# Papra_v0_3.net
KiCad netlist of a schematic drawn in EAGLE
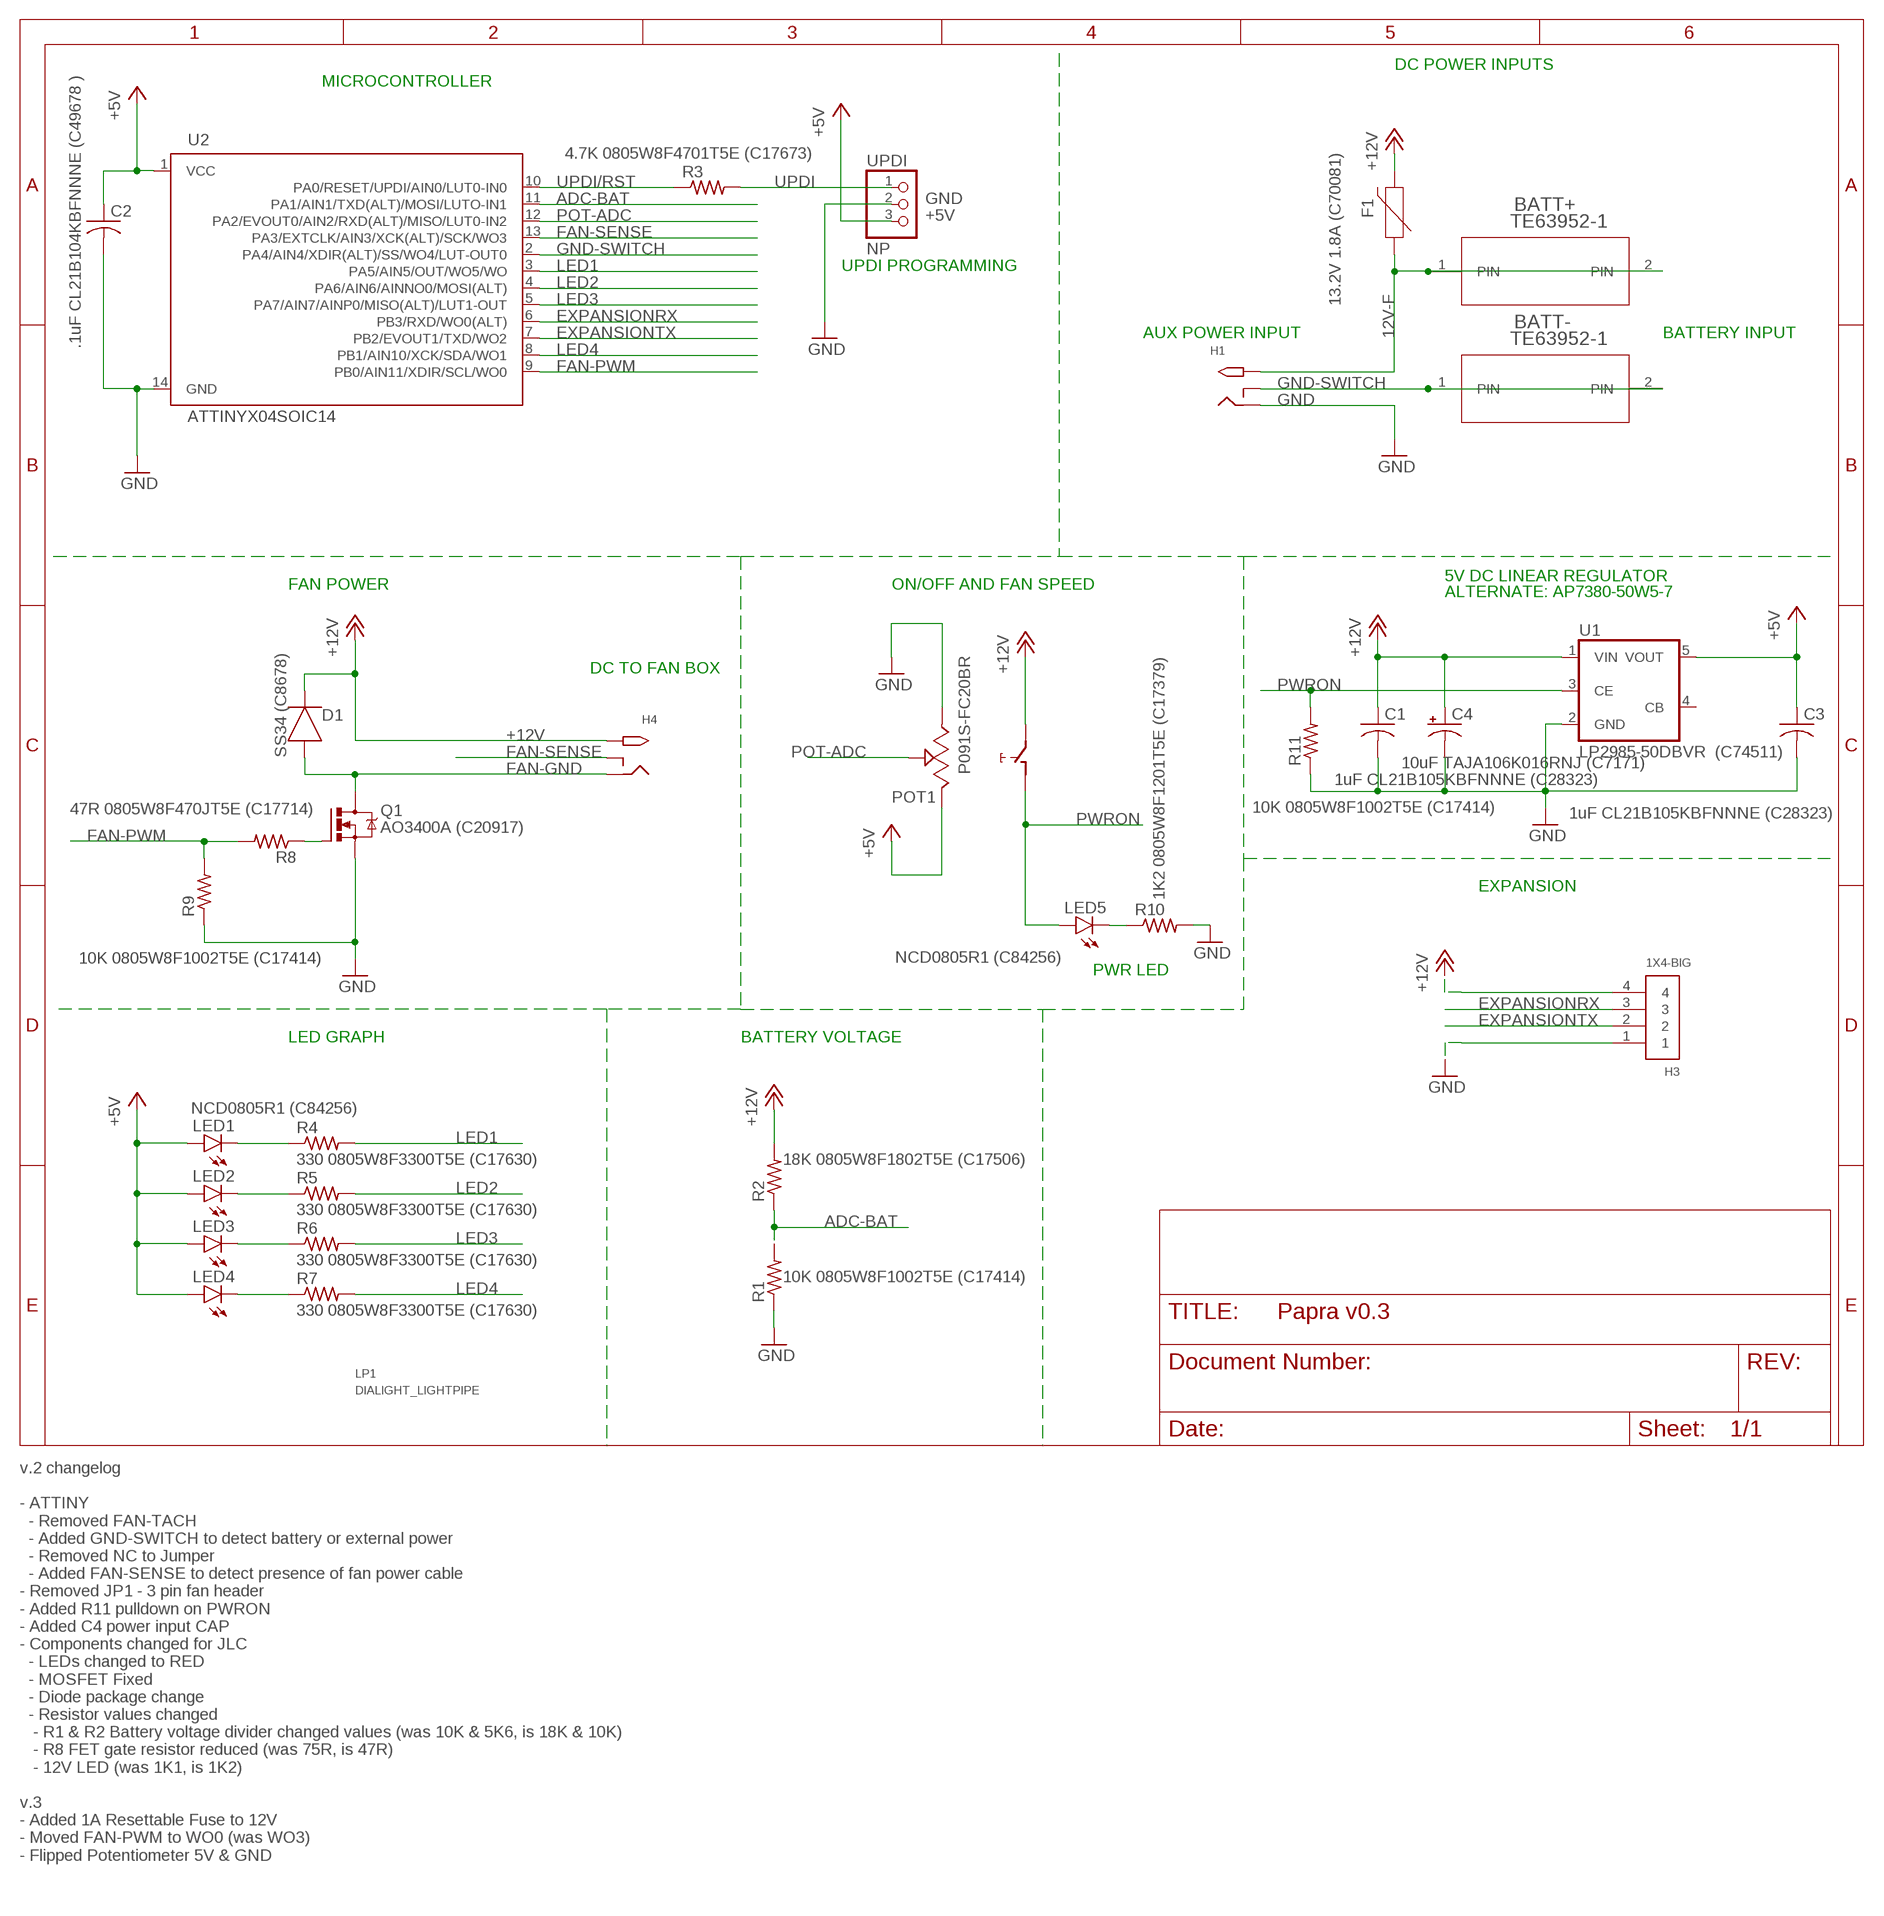
[diagram p0: schematic, sheet 1]

(export (version "E")
  (design (tool "Eeschema 10.0.6"))
  (components
    (comp (ref "BATT+")
      (value "TE63952-1")
      (footprint "eagle-import:TE63952-1")
      (libsource (lib "eagle-import") (part "TE63952-1"))
    )
    (comp (ref "BATT-")
      (value "TE63952-1")
      (footprint "eagle-import:TE63952-1")
      (libsource (lib "eagle-import") (part "TE63952-1"))
    )
    (comp (ref "C1")
      (value "1uF CL21B105KBFNNNE (C28323)")
      (footprint "eagle-import:C0805")
      (libsource (lib "eagle-import") (part "C-USC0805"))
    )
    (comp (ref "C2")
      (value ".1uF CL21B104KBFNNNE (C49678 )")
      (footprint "eagle-import:C0805")
      (libsource (lib "eagle-import") (part "C-USC0805"))
    )
    (comp (ref "C3")
      (value "1uF CL21B105KBFNNNE (C28323)")
      (footprint "eagle-import:C0805")
      (libsource (lib "eagle-import") (part "C-USC0805"))
    )
    (comp (ref "C4")
      (value "10uF TAJA106K016RNJ (C7171)")
      (footprint "eagle-import:A_3216-18R")
      (libsource (lib "eagle-import") (part "CPOL-USA/3216-18R"))
    )
    (comp (ref "D1")
      (value "SS34 (C8678)")
      (footprint "eagle-import:DIOM5226X290N")
      (libsource (lib "eagle-import") (part "DIODEDO-214AC(SMA)"))
    )
    (comp (ref "F1")
      (value "13.2V 1.8A (C70081)")
      (footprint "eagle-import:1206")
      (libsource (lib "eagle-import") (part "PPTC_HALF-AMP"))
    )
    (comp (ref "H1")
      (value "M-CUI-PJ-066A")
      (footprint "eagle-import:DCJACK-PJ-066A")
      (libsource (lib "eagle-import") (part "PJ-066A"))
    )
    (comp (ref "H3")
      (value "1X4-BIG")
      (footprint "eagle-import:1X04-BIG")
      (libsource (lib "eagle-import") (part "1X4-BIG"))
    )
    (comp (ref "H4")
      (value "M-CUI-PJ-066A")
      (footprint "eagle-import:DCJACK-PJ-066A")
      (libsource (lib "eagle-import") (part "PJ-066A"))
    )
    (comp (ref "LED1")
      (value "NCD0805R1 (C84256)")
      (footprint "eagle-import:CHIPLED_0805")
      (libsource (lib "eagle-import") (part "LEDCHIPLED_0805"))
    )
    (comp (ref "LED2")
      (value "NCD0805R1 (C84256)")
      (footprint "eagle-import:CHIPLED_0805")
      (libsource (lib "eagle-import") (part "LEDCHIPLED_0805"))
    )
    (comp (ref "LED3")
      (value "NCD0805R1 (C84256)")
      (footprint "eagle-import:CHIPLED_0805")
      (libsource (lib "eagle-import") (part "LEDCHIPLED_0805"))
    )
    (comp (ref "LED4")
      (value "NCD0805R1 (C84256)")
      (footprint "eagle-import:CHIPLED_0805")
      (libsource (lib "eagle-import") (part "LEDCHIPLED_0805"))
    )
    (comp (ref "LED5")
      (value "NCD0805R1 (C84256)")
      (footprint "eagle-import:CHIPLED_0805")
      (libsource (lib "eagle-import") (part "LEDCHIPLED_0805"))
    )
    (comp (ref "LP1")
      (value "DIALIGHT_LIGHTPIPE")
      (footprint "eagle-import:DIALIGHT_5151020F__LEDS")
      (libsource (lib "eagle-import") (part "DIALIGHT_LIGHTPIPE"))
    )
    (comp (ref "POT1")
      (value "P091S-FC20BR")
      (footprint "eagle-import:P091S-FC20BR")
      (libsource (lib "eagle-import") (part "P091S-FC20BR"))
    )
    (comp (ref "Q1")
      (value "AO3400A (C20917)")
      (footprint "eagle-import:SOT23")
      (fields (field (name "MANUFACTURER") "ON Semiconductor") (field (name "MPN") "BSS123L"))
      (libsource (lib "eagle-import") (part "NMOSFET_-SOT23BSS123"))
    )
    (comp (ref "R1")
      (value "10K 0805W8F1002T5E (C17414)")
      (footprint "eagle-import:R0805")
      (libsource (lib "eagle-import") (part "R-US_R0805"))
    )
    (comp (ref "R2")
      (value "18K 0805W8F1802T5E (C17506)")
      (footprint "eagle-import:R0805")
      (libsource (lib "eagle-import") (part "R-US_R0805"))
    )
    (comp (ref "R3")
      (value "4.7K 0805W8F4701T5E (C17673)")
      (footprint "eagle-import:R0805")
      (libsource (lib "eagle-import") (part "R-US_R0805"))
    )
    (comp (ref "R4")
      (value "330 0805W8F3300T5E (C17630)")
      (footprint "eagle-import:R0805")
      (libsource (lib "eagle-import") (part "R-US_R0805"))
    )
    (comp (ref "R5")
      (value "330 0805W8F3300T5E (C17630)")
      (footprint "eagle-import:R0805")
      (libsource (lib "eagle-import") (part "R-US_R0805"))
    )
    (comp (ref "R6")
      (value "330 0805W8F3300T5E (C17630)")
      (footprint "eagle-import:R0805")
      (libsource (lib "eagle-import") (part "R-US_R0805"))
    )
    (comp (ref "R7")
      (value "330 0805W8F3300T5E (C17630)")
      (footprint "eagle-import:R0805")
      (libsource (lib "eagle-import") (part "R-US_R0805"))
    )
    (comp (ref "R8")
      (value "47R 0805W8F470JT5E (C17714)")
      (footprint "eagle-import:R0805")
      (libsource (lib "eagle-import") (part "R-US_R0805"))
    )
    (comp (ref "R9")
      (value "10K 0805W8F1002T5E (C17414)")
      (footprint "eagle-import:R0805")
      (libsource (lib "eagle-import") (part "R-US_R0805"))
    )
    (comp (ref "R10")
      (value "1K2 0805W8F1201T5E (C17379)")
      (footprint "eagle-import:R0805")
      (libsource (lib "eagle-import") (part "R-US_R0805"))
    )
    (comp (ref "R11")
      (value "10K 0805W8F1002T5E (C17414)")
      (footprint "eagle-import:R0805")
      (libsource (lib "eagle-import") (part "R-US_R0805"))
    )
    (comp (ref "U1")
      (value "LP2985-50DBVR (C74511)")
      (footprint "eagle-import:SOT25")
      (libsource (lib "eagle-import") (part "TS520533"))
    )
    (comp (ref "U2")
      (value "ATTINYX04SOIC14")
      (footprint "eagle-import:SOIC127P600X144-14")
      (libsource (lib "eagle-import") (part "ATTINYX04SOIC14"))
    )
    (comp (ref "UPDI")
      (value "NP")
      (footprint "eagle-import:1X03")
      (libsource (lib "eagle-import") (part "PINHD-1X3"))
    )
  )
  (nets
    (net (code "1") (name "+5V") (class "Default")
      (node (ref "C2") (pin "1") (pinfunction "1_1") (pintype "passive"))
      (node (ref "C3") (pin "1") (pinfunction "1_1") (pintype "passive"))
      (node (ref "LED1") (pin "A") (pinfunction "A_A") (pintype "passive"))
      (node (ref "LED2") (pin "A") (pinfunction "A_A") (pintype "passive"))
      (node (ref "LED3") (pin "A") (pinfunction "A_A") (pintype "passive"))
      (node (ref "LED4") (pin "A") (pinfunction "A_A") (pintype "passive"))
      (node (ref "POT1") (pin "3") (pinfunction "3_3") (pintype "passive"))
      (node (ref "U1") (pin "5") (pinfunction "VOUT_5") (pintype "passive"))
      (node (ref "U2") (pin "1") (pinfunction "VCC_1") (pintype "power_in"))
      (node (ref "UPDI") (pin "3") (pinfunction "3_3") (pintype "passive"))
    )
    (net (code "2") (name "+12V") (class "Default")
      (node (ref "C1") (pin "1") (pinfunction "1_1") (pintype "passive"))
      (node (ref "C4") (pin "+") (pinfunction "+_+") (pintype "passive"))
      (node (ref "D1") (pin "1") (pinfunction "C_1") (pintype "passive"))
      (node (ref "F1") (pin "2") (pinfunction "2_2") (pintype "bidirectional"))
      (node (ref "H3") (pin "4") (pinfunction "4_4") (pintype "bidirectional"))
      (node (ref "H4") (pin "PWR") (pinfunction "TIP_PWR") (pintype "bidirectional"))
      (node (ref "POT1") (pin "NO") (pinfunction "5_NO") (pintype "passive"))
      (node (ref "R2") (pin "2") (pinfunction "2_2") (pintype "passive"))
      (node (ref "U1") (pin "1") (pinfunction "VIN_1") (pintype "input"))
    )
    (net (code "3") (name "/12V-F") (class "Default")
      (node (ref "BATT+") (pin "1") (pinfunction "PIN_1") (pintype "passive"))
      (node (ref "BATT+") (pin "2") (pinfunction "PIN_2") (pintype "passive"))
      (node (ref "F1") (pin "1") (pinfunction "1_1") (pintype "bidirectional"))
      (node (ref "H1") (pin "PWR") (pinfunction "TIP_PWR") (pintype "bidirectional"))
    )
    (net (code "4") (name "/ADC-BAT") (class "Default")
      (node (ref "R1") (pin "2") (pinfunction "2_2") (pintype "passive"))
      (node (ref "R2") (pin "1") (pinfunction "1_1") (pintype "passive"))
      (node (ref "U2") (pin "11") (pinfunction "PA1/AIN1/TXD(ALT)/MOSI/LUTO-IN1_11") (pintype "bidirectional"))
    )
    (net (code "5") (name "/EXPANSIONRX") (class "Default")
      (node (ref "H3") (pin "3") (pinfunction "3_3") (pintype "bidirectional"))
      (node (ref "U2") (pin "6") (pinfunction "PB3/RXD/WO0(ALT)_6") (pintype "bidirectional"))
    )
    (net (code "6") (name "/EXPANSIONTX") (class "Default")
      (node (ref "H3") (pin "2") (pinfunction "2_2") (pintype "bidirectional"))
      (node (ref "U2") (pin "7") (pinfunction "PB2/EVOUT1/TXD/WO2_7") (pintype "bidirectional"))
    )
    (net (code "7") (name "/FAN-GND") (class "Default")
      (node (ref "D1") (pin "2") (pinfunction "A_2") (pintype "passive"))
      (node (ref "H4") (pin "GND") (pinfunction "RING_GND") (pintype "bidirectional"))
      (node (ref "Q1") (pin "3") (pinfunction "D_3") (pintype "passive"))
    )
    (net (code "8") (name "/FAN-PWM") (class "Default")
      (node (ref "R8") (pin "2") (pinfunction "2_2") (pintype "passive"))
      (node (ref "R9") (pin "2") (pinfunction "2_2") (pintype "passive"))
      (node (ref "U2") (pin "9") (pinfunction "PB0/AIN11/XDIR/SCL/WO0_9") (pintype "bidirectional"))
    )
    (net (code "9") (name "/FAN-SENSE") (class "Default")
      (node (ref "H4") (pin "GNDBREAK") (pinfunction "RING_SW_GNDBREAK") (pintype "bidirectional"))
      (node (ref "U2") (pin "13") (pinfunction "PA3/EXTCLK/AIN3/XCK(ALT)/SCK/WO3_13") (pintype "bidirectional"))
    )
    (net (code "10") (name "/GND-SWITCH") (class "Default")
      (node (ref "BATT-") (pin "1") (pinfunction "PIN_1") (pintype "passive"))
      (node (ref "BATT-") (pin "2") (pinfunction "PIN_2") (pintype "passive"))
      (node (ref "H1") (pin "GNDBREAK") (pinfunction "RING_SW_GNDBREAK") (pintype "bidirectional"))
      (node (ref "U2") (pin "2") (pinfunction "PA4/AIN4/XDIR(ALT)/SS/WO4/LUT-OUT0_2") (pintype "bidirectional"))
    )
    (net (code "11") (name "/LED1") (class "Default")
      (node (ref "R4") (pin "2") (pinfunction "2_2") (pintype "passive"))
      (node (ref "U2") (pin "3") (pinfunction "PA5/AIN5/OUT/WO5/WO_3") (pintype "bidirectional"))
    )
    (net (code "12") (name "/LED2") (class "Default")
      (node (ref "R5") (pin "2") (pinfunction "2_2") (pintype "passive"))
      (node (ref "U2") (pin "4") (pinfunction "PA6/AIN6/AINNO0/MOSI(ALT)_4") (pintype "bidirectional"))
    )
    (net (code "13") (name "/LED3") (class "Default")
      (node (ref "R6") (pin "2") (pinfunction "2_2") (pintype "passive"))
      (node (ref "U2") (pin "5") (pinfunction "PA7/AIN7/AINP0/MISO(ALT)/LUT1-OUT_5") (pintype "bidirectional"))
    )
    (net (code "14") (name "/LED4") (class "Default")
      (node (ref "R7") (pin "2") (pinfunction "2_2") (pintype "passive"))
      (node (ref "U2") (pin "8") (pinfunction "PB1/AIN10/XCK/SDA/WO1_8") (pintype "bidirectional"))
    )
    (net (code "15") (name "/POT-ADC") (class "Default")
      (node (ref "POT1") (pin "2") (pinfunction "2_2") (pintype "passive"))
      (node (ref "U2") (pin "12") (pinfunction "PA2/EVOUT0/AIN2/RXD(ALT)/MISO/LUT0-IN2_12") (pintype "bidirectional"))
    )
    (net (code "16") (name "/PWRON") (class "Default")
      (node (ref "LED5") (pin "A") (pinfunction "A_A") (pintype "passive"))
      (node (ref "POT1") (pin "COM") (pinfunction "4_COM") (pintype "passive"))
      (node (ref "R11") (pin "2") (pinfunction "2_2") (pintype "passive"))
      (node (ref "U1") (pin "3") (pinfunction "CE_3") (pintype "input"))
    )
    (net (code "17") (name "/UPDI") (class "Default")
      (node (ref "R3") (pin "2") (pinfunction "2_2") (pintype "passive"))
      (node (ref "UPDI") (pin "1") (pinfunction "1_1") (pintype "passive"))
    )
    (net (code "18") (name "/UPDI{slash}RST") (class "Default")
      (node (ref "R3") (pin "1") (pinfunction "1_1") (pintype "passive"))
      (node (ref "U2") (pin "10") (pinfunction "PA0/RESET/UPDI/AIN0/LUT0-IN0_10") (pintype "bidirectional"))
    )
    (net (code "19") (name "GND") (class "Default")
      (node (ref "C1") (pin "2") (pinfunction "2_2") (pintype "passive"))
      (node (ref "C2") (pin "2") (pinfunction "2_2") (pintype "passive"))
      (node (ref "C3") (pin "2") (pinfunction "2_2") (pintype "passive"))
      (node (ref "C4") (pin "-") (pinfunction "-_-") (pintype "passive"))
      (node (ref "H1") (pin "GND") (pinfunction "RING_GND") (pintype "bidirectional"))
      (node (ref "H3") (pin "1") (pinfunction "1_1") (pintype "bidirectional"))
      (node (ref "POT1") (pin "1") (pinfunction "1_1") (pintype "passive"))
      (node (ref "Q1") (pin "2") (pinfunction "S_2") (pintype "passive"))
      (node (ref "R1") (pin "1") (pinfunction "1_1") (pintype "passive"))
      (node (ref "R10") (pin "2") (pinfunction "2_2") (pintype "passive"))
      (node (ref "R11") (pin "1") (pinfunction "1_1") (pintype "passive"))
      (node (ref "R9") (pin "1") (pinfunction "1_1") (pintype "passive"))
      (node (ref "U1") (pin "2") (pinfunction "GND_2") (pintype "passive"))
      (node (ref "U2") (pin "14") (pinfunction "GND_14") (pintype "power_in"))
      (node (ref "UPDI") (pin "2") (pinfunction "2_2") (pintype "passive"))
    )
    (net (code "20") (name "Net-(LED1-PadC)") (class "Default")
      (node (ref "LED1") (pin "C") (pinfunction "C_C") (pintype "passive"))
      (node (ref "R4") (pin "1") (pinfunction "1_1") (pintype "passive"))
    )
    (net (code "21") (name "Net-(LED2-PadC)") (class "Default")
      (node (ref "LED2") (pin "C") (pinfunction "C_C") (pintype "passive"))
      (node (ref "R5") (pin "1") (pinfunction "1_1") (pintype "passive"))
    )
    (net (code "22") (name "Net-(LED3-PadC)") (class "Default")
      (node (ref "LED3") (pin "C") (pinfunction "C_C") (pintype "passive"))
      (node (ref "R6") (pin "1") (pinfunction "1_1") (pintype "passive"))
    )
    (net (code "23") (name "Net-(LED4-PadC)") (class "Default")
      (node (ref "LED4") (pin "C") (pinfunction "C_C") (pintype "passive"))
      (node (ref "R7") (pin "1") (pinfunction "1_1") (pintype "passive"))
    )
    (net (code "24") (name "Net-(LED5-PadC)") (class "Default")
      (node (ref "LED5") (pin "C") (pinfunction "C_C") (pintype "passive"))
      (node (ref "R10") (pin "1") (pinfunction "1_1") (pintype "passive"))
    )
    (net (code "25") (name "Net-(Q1-G)") (class "Default")
      (node (ref "Q1") (pin "1") (pinfunction "G_1") (pintype "passive"))
      (node (ref "R8") (pin "1") (pinfunction "1_1") (pintype "passive"))
    )
    (net (code "26") (name "unconnected-(U1-CB-Pad4)") (class "Default")
      (node (ref "U1") (pin "4") (pinfunction "CB_4") (pintype "input"))
    )
  )
)
